# IO_Connector.net
KiCad netlist of a schematic drawn in Altium Designer
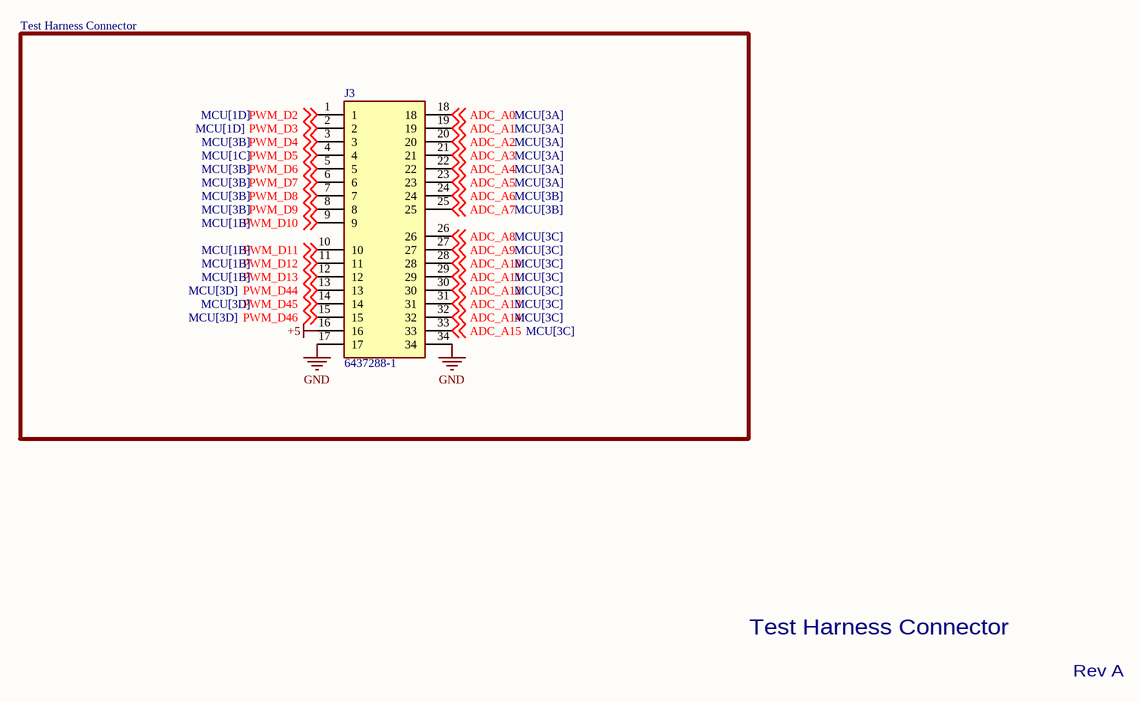
[diagram p0: IO Connector.SchDoc]

(export (version "E")
  (design (tool "Eeschema 10.0.6"))
  (components
    (comp (ref "J3")
      (value "6437288-1")
      (footprint "6437288-1:TE_6437288-1")
      (description "34 Position 4 Row Right Angle Receptacle Through Hole Super Seal Cap Assy")
      (fields (field (name "MF") "{'manufacturer': u'TE Connectivity'}"))
      (libsource (lib "6437288-1") (part "6437288-1"))
    )
  )
  (nets
    (net (code "1") (name "+5") (class "Default")
      (node (ref "J3") (pin "16") (pinfunction "16_16") (pintype "passive"))
    )
    (net (code "2") (name "ADC_A0") (class "Default")
      (node (ref "J3") (pin "18") (pinfunction "18_18") (pintype "passive"))
    )
    (net (code "3") (name "ADC_A1") (class "Default")
      (node (ref "J3") (pin "19") (pinfunction "19_19") (pintype "passive"))
    )
    (net (code "4") (name "ADC_A2") (class "Default")
      (node (ref "J3") (pin "20") (pinfunction "20_20") (pintype "passive"))
    )
    (net (code "5") (name "ADC_A3") (class "Default")
      (node (ref "J3") (pin "21") (pinfunction "21_21") (pintype "passive"))
    )
    (net (code "6") (name "ADC_A4") (class "Default")
      (node (ref "J3") (pin "22") (pinfunction "22_22") (pintype "passive"))
    )
    (net (code "7") (name "ADC_A5") (class "Default")
      (node (ref "J3") (pin "23") (pinfunction "23_23") (pintype "passive"))
    )
    (net (code "8") (name "ADC_A6") (class "Default")
      (node (ref "J3") (pin "24") (pinfunction "24_24") (pintype "passive"))
    )
    (net (code "9") (name "ADC_A7") (class "Default")
      (node (ref "J3") (pin "25") (pinfunction "25_25") (pintype "passive"))
    )
    (net (code "10") (name "ADC_A8") (class "Default")
      (node (ref "J3") (pin "26") (pinfunction "26_26") (pintype "passive"))
    )
    (net (code "11") (name "ADC_A9") (class "Default")
      (node (ref "J3") (pin "27") (pinfunction "27_27") (pintype "passive"))
    )
    (net (code "12") (name "ADC_A10") (class "Default")
      (node (ref "J3") (pin "28") (pinfunction "28_28") (pintype "passive"))
    )
    (net (code "13") (name "ADC_A11") (class "Default")
      (node (ref "J3") (pin "29") (pinfunction "29_29") (pintype "passive"))
    )
    (net (code "14") (name "ADC_A12") (class "Default")
      (node (ref "J3") (pin "30") (pinfunction "30_30") (pintype "passive"))
    )
    (net (code "15") (name "ADC_A13") (class "Default")
      (node (ref "J3") (pin "31") (pinfunction "31_31") (pintype "passive"))
    )
    (net (code "16") (name "ADC_A14") (class "Default")
      (node (ref "J3") (pin "32") (pinfunction "32_32") (pintype "passive"))
    )
    (net (code "17") (name "ADC_A15") (class "Default")
      (node (ref "J3") (pin "33") (pinfunction "33_33") (pintype "passive"))
    )
    (net (code "18") (name "GND") (class "Default")
      (node (ref "J3") (pin "17") (pinfunction "17_17") (pintype "passive"))
      (node (ref "J3") (pin "34") (pinfunction "34_34") (pintype "passive"))
    )
    (net (code "19") (name "PWM_D2") (class "Default")
      (node (ref "J3") (pin "1") (pinfunction "1_1") (pintype "passive"))
    )
    (net (code "20") (name "PWM_D3") (class "Default")
      (node (ref "J3") (pin "2") (pinfunction "2_2") (pintype "passive"))
    )
    (net (code "21") (name "PWM_D4") (class "Default")
      (node (ref "J3") (pin "3") (pinfunction "3_3") (pintype "passive"))
    )
    (net (code "22") (name "PWM_D5") (class "Default")
      (node (ref "J3") (pin "4") (pinfunction "4_4") (pintype "passive"))
    )
    (net (code "23") (name "PWM_D6") (class "Default")
      (node (ref "J3") (pin "5") (pinfunction "5_5") (pintype "passive"))
    )
    (net (code "24") (name "PWM_D7") (class "Default")
      (node (ref "J3") (pin "6") (pinfunction "6_6") (pintype "passive"))
    )
    (net (code "25") (name "PWM_D8") (class "Default")
      (node (ref "J3") (pin "7") (pinfunction "7_7") (pintype "passive"))
    )
    (net (code "26") (name "PWM_D9") (class "Default")
      (node (ref "J3") (pin "8") (pinfunction "8_8") (pintype "passive"))
    )
    (net (code "27") (name "PWM_D10") (class "Default")
      (node (ref "J3") (pin "9") (pinfunction "9_9") (pintype "passive"))
    )
    (net (code "28") (name "PWM_D11") (class "Default")
      (node (ref "J3") (pin "10") (pinfunction "10_10") (pintype "passive"))
    )
    (net (code "29") (name "PWM_D12") (class "Default")
      (node (ref "J3") (pin "11") (pinfunction "11_11") (pintype "passive"))
    )
    (net (code "30") (name "PWM_D13") (class "Default")
      (node (ref "J3") (pin "12") (pinfunction "12_12") (pintype "passive"))
    )
    (net (code "31") (name "PWM_D44") (class "Default")
      (node (ref "J3") (pin "13") (pinfunction "13_13") (pintype "passive"))
    )
    (net (code "32") (name "PWM_D45") (class "Default")
      (node (ref "J3") (pin "14") (pinfunction "14_14") (pintype "passive"))
    )
    (net (code "33") (name "PWM_D46") (class "Default")
      (node (ref "J3") (pin "15") (pinfunction "15_15") (pintype "passive"))
    )
  )
)
